# Battery.net
KiCad netlist of a schematic drawn in Altium Designer
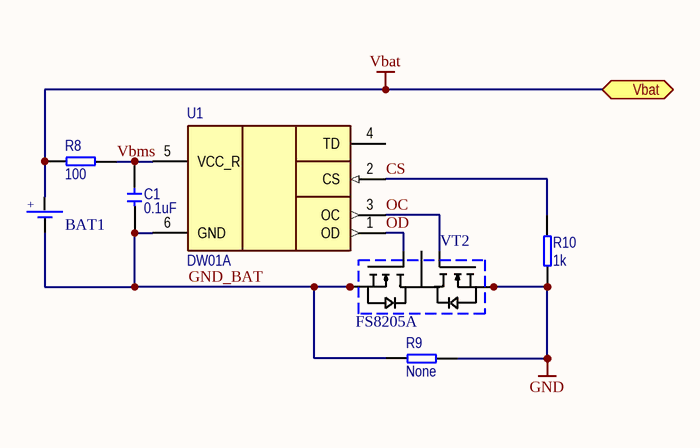
[diagram p0: Battery.SchDoc]

(export (version "E")
  (design (tool "Eeschema 10.0.6"))
  (components
    (comp (ref "BAT1")
      (value "18350+clipses")
      (footprint "BAT_18350_CLIPS")
      (description "generic battery")
      (libsource (lib "power") (part "!Battery"))
    )
    (comp (ref "C1")
      (value "0.1uF")
      (footprint "CERCAP 0402")
      (description "Capacitor")
      (fields (field (name "VOLTAGE") "10V") (field (name "Comment") "CERCAP 0402 0.1uF 10V X7R"))
      (libsource (lib "!main") (part "!Capacitor"))
    )
    (comp (ref "R8")
      (value "100")
      (footprint "RES 0402")
      (description "Resistor")
      (fields (field (name "Comment") "RES 0402 100"))
      (libsource (lib "!main") (part "!Resistor"))
    )
    (comp (ref "R9")
      (value "None")
      (footprint "RES 0603")
      (description "Resistor")
      (fields (field (name "Comment") "RES 0603 None"))
      (libsource (lib "!main") (part "!Resistor"))
    )
    (comp (ref "R10")
      (value "1k")
      (footprint "RES 0402")
      (description "Resistor")
      (fields (field (name "Comment") "RES 0402 1k"))
      (libsource (lib "!main") (part "!Resistor"))
    )
    (comp (ref "U1")
      (value "DW01A")
      (footprint "SOT23-6")
      (description "BMS")
      (libsource (lib "power") (part "DW01A"))
    )
    (comp (ref "VT2")
      (value "FS8205A")
      (footprint "TSSOP-8")
      (description "double N-ch")
      (libsource (lib "transistors") (part "FS8205A"))
    )
  )
  (nets
    (net (code "1") (name "/CS") (class "Default")
      (node (ref "R10") (pin "2") (pinfunction "12_2") (pintype "passive"))
      (node (ref "U1") (pin "2") (pinfunction "CS_2") (pintype "input"))
    )
    (net (code "2") (name "/GND_BAT") (class "Default")
      (node (ref "BAT1") (pin "K") (pintype "passive"))
      (node (ref "C1") (pin "1") (pintype "passive"))
      (node (ref "R9") (pin "2") (pinfunction "12_2") (pintype "passive"))
      (node (ref "U1") (pin "6") (pinfunction "GND_6") (pintype "power_in"))
      (node (ref "VT2") (pin "2") (pinfunction "3_2") (pintype "passive"))
      (node (ref "VT2") (pin "3") (pinfunction "4_3") (pintype "passive"))
    )
    (net (code "3") (name "/OC") (class "Default")
      (node (ref "U1") (pin "3") (pinfunction "OC_3") (pintype "output"))
      (node (ref "VT2") (pin "5") (pinfunction "5_5") (pintype "passive"))
    )
    (net (code "4") (name "/OD") (class "Default")
      (node (ref "U1") (pin "1") (pinfunction "OD_1") (pintype "output"))
      (node (ref "VT2") (pin "4") (pinfunction "4_4") (pintype "passive"))
    )
    (net (code "5") (name "/Vbms") (class "Default")
      (node (ref "C1") (pin "2") (pintype "passive"))
      (node (ref "R8") (pin "2") (pinfunction "12_2") (pintype "passive"))
      (node (ref "U1") (pin "5") (pinfunction "VCC_R_5") (pintype "power_in"))
    )
    (net (code "6") (name "GND") (class "Default")
      (node (ref "R10") (pin "1") (pinfunction "11_1") (pintype "passive"))
      (node (ref "R9") (pin "1") (pinfunction "11_1") (pintype "passive"))
      (node (ref "VT2") (pin "6") (pinfunction "7_6") (pintype "passive"))
      (node (ref "VT2") (pin "7") (pinfunction "6_7") (pintype "passive"))
    )
    (net (code "7") (name "Net-(VT2-2)") (class "Default")
      (node (ref "VT2") (pin "1") (pinfunction "1_1") (pintype "passive"))
      (node (ref "VT2") (pin "8") (pinfunction "2_8") (pintype "passive"))
    )
    (net (code "8") (name "Vbat") (class "Default")
      (node (ref "BAT1") (pin "A") (pintype "passive"))
      (node (ref "R8") (pin "1") (pinfunction "11_1") (pintype "passive"))
    )
    (net (code "9") (name "unconnected-(U1-TD-Pad4)") (class "Default")
      (node (ref "U1") (pin "4") (pinfunction "TD_4") (pintype "passive"))
    )
  )
)
